# 04_AudioCodec.net
KiCad netlist of a schematic drawn in Altium Designer
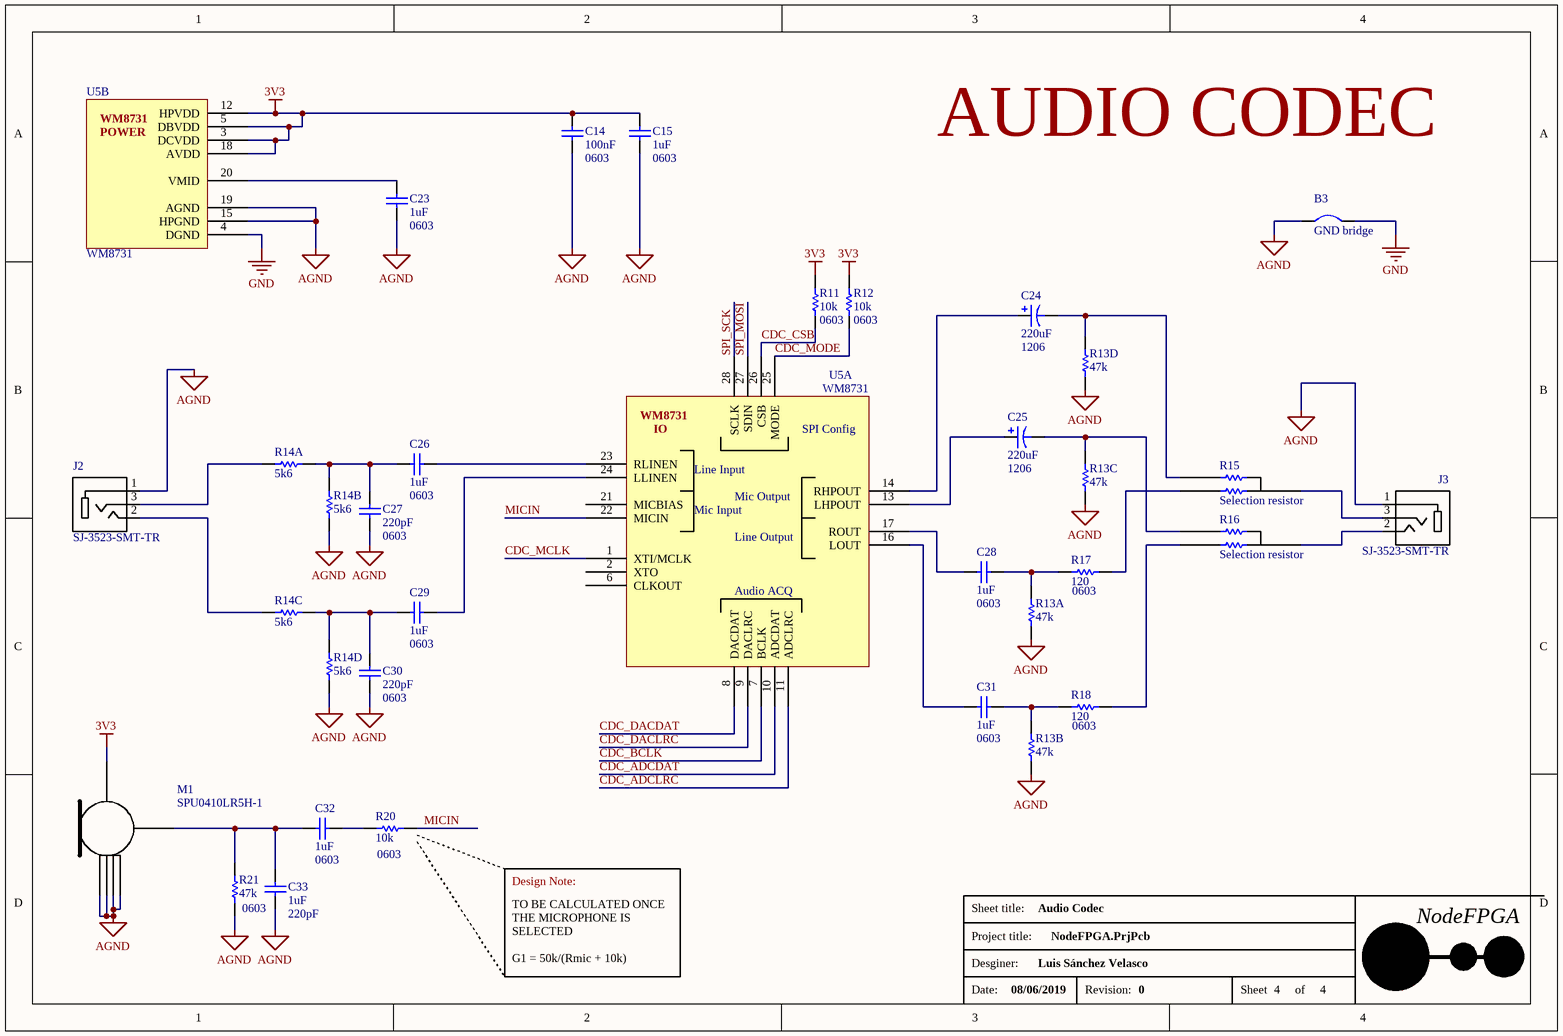
[diagram p0: 04_AudioCodec.SchDoc]

(export (version "E")
  (design (tool "Eeschema 10.0.6"))
  (components
    (comp (ref "B3") (value "GND bridge") (footprint "Bridge") (libsource (lib "NodeFPGA") (part "Bridge")))
    (comp (ref "C14")
      (value "100nF")
      (footprint "0603 CAP")
      (description "Capacitor")
      (fields (field (name "PACKAGE") "0603") (field (name "Comment") "Ceramic capacitor"))
      (libsource (lib "NodeFPGA") (part "Capacitor"))
    )
    (comp (ref "C15")
      (value "1uF")
      (footprint "0603 CAP")
      (description "Capacitor")
      (fields (field (name "PACKAGE") "0603") (field (name "Comment") "Ceramic capacitor"))
      (libsource (lib "NodeFPGA") (part "Capacitor"))
    )
    (comp (ref "C23")
      (value "1uF")
      (footprint "0603 CAP")
      (description "Capacitor")
      (fields (field (name "PACKAGE") "0603") (field (name "Comment") "Ceramic capacitor"))
      (libsource (lib "NodeFPGA") (part "Capacitor"))
    )
    (comp (ref "C24")
      (value "220uF")
      (footprint "CAPCP3216X16N")
      (description "Capacitor Electrolitic")
      (fields (field (name "PACKAGE") "1206") (field (name "AUTHOR") "Jaime Jiménez Ortega"))
      (libsource (lib "NodeFPGA") (part "Capacitor Electrolitic"))
    )
    (comp (ref "C25")
      (value "220uF")
      (footprint "CAPCP3216X16N")
      (description "Capacitor Electrolitic")
      (fields (field (name "PACKAGE") "1206") (field (name "AUTHOR") "Jaime Jiménez Ortega"))
      (libsource (lib "NodeFPGA") (part "Capacitor Electrolitic"))
    )
    (comp (ref "C26")
      (value "1uF")
      (footprint "0603 CAP")
      (description "Capacitor")
      (fields (field (name "PACKAGE") "0603") (field (name "Comment") "Ceramic capacitor"))
      (libsource (lib "NodeFPGA") (part "Capacitor"))
    )
    (comp (ref "C27")
      (value "220pF")
      (footprint "0603 CAP")
      (description "Capacitor")
      (fields (field (name "PACKAGE") "0603") (field (name "Comment") "Ceramic capacitor"))
      (libsource (lib "NodeFPGA") (part "Capacitor"))
    )
    (comp (ref "C28")
      (value "1uF")
      (footprint "0603 CAP")
      (description "Capacitor")
      (fields (field (name "PACKAGE") "0603") (field (name "Comment") "Ceramic capacitor"))
      (libsource (lib "NodeFPGA") (part "Capacitor"))
    )
    (comp (ref "C29")
      (value "1uF")
      (footprint "0603 CAP")
      (description "Capacitor")
      (fields (field (name "PACKAGE") "0603") (field (name "Comment") "Ceramic capacitor"))
      (libsource (lib "NodeFPGA") (part "Capacitor"))
    )
    (comp (ref "C30")
      (value "220pF")
      (footprint "0603 CAP")
      (description "Capacitor")
      (fields (field (name "PACKAGE") "0603") (field (name "Comment") "Ceramic capacitor"))
      (libsource (lib "NodeFPGA") (part "Capacitor"))
    )
    (comp (ref "C31")
      (value "1uF")
      (footprint "0603 CAP")
      (description "Capacitor")
      (fields (field (name "PACKAGE") "0603") (field (name "Comment") "Ceramic capacitor"))
      (libsource (lib "NodeFPGA") (part "Capacitor"))
    )
    (comp (ref "C32")
      (value "1uF")
      (footprint "0603 CAP")
      (description "Capacitor")
      (fields (field (name "PACKAGE") "0603") (field (name "Comment") "Ceramic capacitor"))
      (libsource (lib "NodeFPGA") (part "Capacitor"))
    )
    (comp (ref "C33")
      (value "1uF")
      (footprint "0603 CAP")
      (description "Capacitor")
      (fields (field (name "PACKAGE") "220pF") (field (name "Comment") "Ceramic capacitor"))
      (libsource (lib "NodeFPGA") (part "Capacitor"))
    )
    (comp (ref "J2")
      (value "SJ-3523-SMT-TR")
      (footprint "CUI_SJ-3523-SMT-TR")
      (libsource (lib "NodeFPGA") (part "SJ-3523-SMT-TR"))
    )
    (comp (ref "J3")
      (value "SJ-3523-SMT-TR")
      (footprint "CUI_SJ-3523-SMT-TR")
      (libsource (lib "NodeFPGA") (part "SJ-3523-SMT-TR"))
    )
    (comp (ref "M1")
      (value "SPU0410LR5H-1")
      (footprint "SPU0410LR5H-1")
      (description "MEMS Microphone")
      (libsource (lib "NodeFPGA") (part "SPU0410LR5H-1"))
    )
    (comp (ref "R11")
      (value "10k")
      (footprint "Resistencia 0603")
      (description "Resistor")
      (fields (field (name "PACKAGE") "0603"))
      (libsource (lib "NodeFPGA") (part "Resistor"))
    )
    (comp (ref "R12")
      (value "10k")
      (footprint "Resistencia 0603")
      (description "Resistor")
      (fields (field (name "PACKAGE") "0603"))
      (libsource (lib "NodeFPGA") (part "Resistor"))
    )
    (comp (ref "R13")
      (value "47k")
      (description "4 resistors in smd array configuration")
      (fields (field (name "Comment") "Resistor array"))
      (libsource (lib "NodeFPGA") (part "ResistorArray_4"))
    )
    (comp (ref "R14")
      (value "5k6")
      (description "4 resistors in smd array configuration")
      (fields (field (name "Comment") "Resistor array"))
      (libsource (lib "NodeFPGA") (part "ResistorArray_4"))
    )
    (comp (ref "R15") (value "Selection resistor") (libsource (lib "NodeFPGA") (part "SelectionResistor")))
    (comp (ref "R16") (value "Selection resistor") (libsource (lib "NodeFPGA") (part "SelectionResistor")))
    (comp (ref "R17")
      (value "120")
      (footprint "Resistencia 0603")
      (description "Resistor")
      (fields (field (name "PACKAGE") "0603"))
      (libsource (lib "NodeFPGA") (part "Resistor"))
    )
    (comp (ref "R18")
      (value "120")
      (footprint "Resistencia 0603")
      (description "Resistor")
      (fields (field (name "PACKAGE") "0603"))
      (libsource (lib "NodeFPGA") (part "Resistor"))
    )
    (comp (ref "R20")
      (value "10k")
      (footprint "Resistencia 0603")
      (description "Resistor")
      (fields (field (name "PACKAGE") "0603"))
      (libsource (lib "NodeFPGA") (part "Resistor"))
    )
    (comp (ref "R21")
      (value "47k")
      (footprint "Resistencia 0603")
      (description "Resistor")
      (fields (field (name "PACKAGE") "0603"))
      (libsource (lib "NodeFPGA") (part "Resistor"))
    )
    (comp (ref "U5")
      (value "WM8731")
      (footprint "WM8731")
      (description "Portable Internet Audio CODEC with Headphone Driver  and Programmable Sample Rates")
      (libsource (lib "NodeFPGA") (part "WM8731"))
    )
  )
  (nets
    (net (code "1") (name "/CDC_ADCDAT") (class "Default")
      (node (ref "U5") (pin "10") (pinfunction "ADCDAT_10") (pintype "passive"))
    )
    (net (code "2") (name "/CDC_ADCLRC") (class "Default")
      (node (ref "U5") (pin "11") (pinfunction "ADCLRC_11") (pintype "passive"))
    )
    (net (code "3") (name "/CDC_BCLK") (class "Default")
      (node (ref "U5") (pin "7") (pinfunction "BCLK_7") (pintype "passive"))
    )
    (net (code "4") (name "/CDC_CSB") (class "Default")
      (node (ref "R11") (pin "1") (pinfunction "1_1") (pintype "passive"))
      (node (ref "U5") (pin "26") (pinfunction "CSB_26") (pintype "passive"))
    )
    (net (code "5") (name "/CDC_DACDAT") (class "Default")
      (node (ref "U5") (pin "8") (pinfunction "DACDAT_8") (pintype "passive"))
    )
    (net (code "6") (name "/CDC_DACLRC") (class "Default")
      (node (ref "U5") (pin "9") (pinfunction "DACLRC_9") (pintype "passive"))
    )
    (net (code "7") (name "/CDC_MCLK") (class "Default")
      (node (ref "U5") (pin "1") (pinfunction "XTI/MCLK_1") (pintype "passive"))
    )
    (net (code "8") (name "/CDC_MODE") (class "Default")
      (node (ref "R12") (pin "1") (pinfunction "1_1") (pintype "passive"))
      (node (ref "U5") (pin "25") (pinfunction "MODE_25") (pintype "passive"))
    )
    (net (code "9") (name "/MICIN") (class "Default")
      (node (ref "R20") (pin "2") (pinfunction "2_2") (pintype "passive"))
      (node (ref "U5") (pin "22") (pinfunction "MICIN_22") (pintype "passive"))
    )
    (net (code "10") (name "/SPI_MOSI") (class "Default")
      (node (ref "U5") (pin "27") (pinfunction "SDIN_27") (pintype "passive"))
    )
    (net (code "11") (name "/SPI_SCK") (class "Default")
      (node (ref "U5") (pin "28") (pinfunction "SCLK_28") (pintype "passive"))
    )
    (net (code "12") (name "3V3") (class "Default")
      (node (ref "C14") (pin "1") (pinfunction "1_1") (pintype "passive"))
      (node (ref "C15") (pin "1") (pinfunction "1_1") (pintype "passive"))
      (node (ref "M1") (pin "4") (pinfunction "4_4") (pintype "passive"))
      (node (ref "R11") (pin "2") (pinfunction "2_2") (pintype "passive"))
      (node (ref "R12") (pin "2") (pinfunction "2_2") (pintype "passive"))
      (node (ref "U5") (pin "12") (pinfunction "HPVDD_12") (pintype "passive"))
      (node (ref "U5") (pin "18") (pinfunction "AVDD_18") (pintype "passive"))
      (node (ref "U5") (pin "3") (pinfunction "DCVDD_3") (pintype "passive"))
      (node (ref "U5") (pin "5") (pinfunction "DBVDD_5") (pintype "passive"))
    )
    (net (code "13") (name "AGND") (class "Default")
      (node (ref "B3") (pin "1") (pinfunction "1_1") (pintype "passive"))
      (node (ref "C14") (pin "2") (pinfunction "2_2") (pintype "passive"))
      (node (ref "C15") (pin "2") (pinfunction "2_2") (pintype "passive"))
      (node (ref "C23") (pin "2") (pinfunction "2_2") (pintype "passive"))
      (node (ref "C27") (pin "2") (pinfunction "2_2") (pintype "passive"))
      (node (ref "C30") (pin "2") (pinfunction "2_2") (pintype "passive"))
      (node (ref "C33") (pin "2") (pinfunction "2_2") (pintype "passive"))
      (node (ref "J2") (pin "1") (pinfunction "1_1") (pintype "passive"))
      (node (ref "J3") (pin "1") (pinfunction "1_1") (pintype "passive"))
      (node (ref "M1") (pin "2") (pinfunction "2_2") (pintype "passive"))
      (node (ref "M1") (pin "3") (pinfunction "3_3") (pintype "passive"))
      (node (ref "M1") (pin "5") (pinfunction "5_5") (pintype "passive"))
      (node (ref "M1") (pin "6") (pinfunction "6_6") (pintype "passive"))
      (node (ref "R13") (pin "5") (pinfunction "5_5") (pintype "passive"))
      (node (ref "R13") (pin "6") (pinfunction "6_6") (pintype "passive"))
      (node (ref "R13") (pin "7") (pinfunction "7_7") (pintype "passive"))
      (node (ref "R13") (pin "8") (pinfunction "8_8") (pintype "passive"))
      (node (ref "R14") (pin "2") (pinfunction "2_2") (pintype "passive"))
      (node (ref "R14") (pin "4") (pinfunction "4_4") (pintype "passive"))
      (node (ref "R21") (pin "1") (pinfunction "1_1") (pintype "passive"))
      (node (ref "U5") (pin "15") (pinfunction "HPGND_15") (pintype "passive"))
      (node (ref "U5") (pin "19") (pinfunction "AGND_19") (pintype "passive"))
    )
    (net (code "14") (name "GND") (class "Default")
      (node (ref "B3") (pin "2") (pinfunction "2_2") (pintype "passive"))
      (node (ref "U5") (pin "4") (pinfunction "DGND_4") (pintype "passive"))
    )
    (net (code "15") (name "Net-(C24-Pad2)") (class "Default")
      (node (ref "C24") (pin "2") (pinfunction "2_2") (pintype "passive"))
      (node (ref "R13") (pin "4") (pinfunction "4_4") (pintype "passive"))
      (node (ref "R15") (pin "1") (pinfunction "1_1") (pintype "passive"))
    )
    (net (code "16") (name "Net-(C25-Pad2)") (class "Default")
      (node (ref "C25") (pin "2") (pinfunction "2_2") (pintype "passive"))
      (node (ref "R13") (pin "3") (pinfunction "3_3") (pintype "passive"))
      (node (ref "R16") (pin "1") (pinfunction "1_1") (pintype "passive"))
    )
    (net (code "17") (name "Net-(C26-Pad1)") (class "Default")
      (node (ref "C26") (pin "1") (pinfunction "1_1") (pintype "passive"))
      (node (ref "C27") (pin "1") (pinfunction "1_1") (pintype "passive"))
      (node (ref "R14") (pin "7") (pinfunction "7_7") (pintype "passive"))
      (node (ref "R14") (pin "8") (pinfunction "8_8") (pintype "passive"))
    )
    (net (code "18") (name "Net-(C28-Pad2)") (class "Default")
      (node (ref "C28") (pin "2") (pinfunction "2_2") (pintype "passive"))
      (node (ref "R13") (pin "1") (pinfunction "1_1") (pintype "passive"))
      (node (ref "R17") (pin "1") (pinfunction "1_1") (pintype "passive"))
    )
    (net (code "19") (name "Net-(C29-Pad2)") (class "Default")
      (node (ref "C29") (pin "2") (pinfunction "2_2") (pintype "passive"))
      (node (ref "C30") (pin "1") (pinfunction "1_1") (pintype "passive"))
      (node (ref "R14") (pin "5") (pinfunction "5_5") (pintype "passive"))
      (node (ref "R14") (pin "6") (pinfunction "6_6") (pintype "passive"))
    )
    (net (code "20") (name "Net-(C31-Pad2)") (class "Default")
      (node (ref "C31") (pin "2") (pinfunction "2_2") (pintype "passive"))
      (node (ref "R13") (pin "2") (pinfunction "2_2") (pintype "passive"))
      (node (ref "R18") (pin "1") (pinfunction "1_1") (pintype "passive"))
    )
    (net (code "21") (name "Net-(C32-Pad1)") (class "Default")
      (node (ref "C32") (pin "1") (pinfunction "1_1") (pintype "passive"))
      (node (ref "R20") (pin "1") (pinfunction "1_1") (pintype "passive"))
    )
    (net (code "22") (name "Net-(C32-Pad2)") (class "Default")
      (node (ref "C32") (pin "2") (pinfunction "2_2") (pintype "passive"))
      (node (ref "C33") (pin "1") (pinfunction "1_1") (pintype "passive"))
      (node (ref "M1") (pin "1") (pinfunction "1_1") (pintype "passive"))
      (node (ref "R21") (pin "2") (pinfunction "2_2") (pintype "passive"))
    )
    (net (code "23") (name "Net-(J2-Pad2)") (class "Default")
      (node (ref "J2") (pin "2") (pinfunction "2_2") (pintype "passive"))
      (node (ref "R14") (pin "3") (pinfunction "3_3") (pintype "passive"))
    )
    (net (code "24") (name "Net-(J2-Pad3)") (class "Default")
      (node (ref "J2") (pin "3") (pinfunction "3_3") (pintype "passive"))
      (node (ref "R14") (pin "1") (pinfunction "1_1") (pintype "passive"))
    )
    (net (code "25") (name "Net-(J3-Pad2)") (class "Default")
      (node (ref "J3") (pin "2") (pinfunction "2_2") (pintype "passive"))
      (node (ref "R16") (pin "2") (pinfunction "2_2") (pintype "passive"))
    )
    (net (code "26") (name "Net-(J3-Pad3)") (class "Default")
      (node (ref "J3") (pin "3") (pinfunction "3_3") (pintype "passive"))
      (node (ref "R15") (pin "2") (pinfunction "2_2") (pintype "passive"))
    )
    (net (code "27") (name "Net-(R15-Pad3)") (class "Default")
      (node (ref "R15") (pin "3") (pinfunction "3_3") (pintype "passive"))
      (node (ref "R17") (pin "2") (pinfunction "2_2") (pintype "passive"))
    )
    (net (code "28") (name "Net-(R16-Pad3)") (class "Default")
      (node (ref "R16") (pin "3") (pinfunction "3_3") (pintype "passive"))
      (node (ref "R18") (pin "2") (pinfunction "2_2") (pintype "passive"))
    )
    (net (code "29") (name "Net-(U5A-LHPOUT)") (class "Default")
      (node (ref "C25") (pin "1") (pinfunction "1_1") (pintype "passive"))
      (node (ref "U5") (pin "13") (pinfunction "LHPOUT_13") (pintype "passive"))
    )
    (net (code "30") (name "Net-(U5A-LLINEN)") (class "Default")
      (node (ref "C29") (pin "1") (pinfunction "1_1") (pintype "passive"))
      (node (ref "U5") (pin "24") (pinfunction "LLINEN_24") (pintype "passive"))
    )
    (net (code "31") (name "Net-(U5A-LOUT)") (class "Default")
      (node (ref "C31") (pin "1") (pinfunction "1_1") (pintype "passive"))
      (node (ref "U5") (pin "16") (pinfunction "LOUT_16") (pintype "passive"))
    )
    (net (code "32") (name "Net-(U5A-RHPOUT)") (class "Default")
      (node (ref "C24") (pin "1") (pinfunction "1_1") (pintype "passive"))
      (node (ref "U5") (pin "14") (pinfunction "RHPOUT_14") (pintype "passive"))
    )
    (net (code "33") (name "Net-(U5A-RLINEN)") (class "Default")
      (node (ref "C26") (pin "2") (pinfunction "2_2") (pintype "passive"))
      (node (ref "U5") (pin "23") (pinfunction "RLINEN_23") (pintype "passive"))
    )
    (net (code "34") (name "Net-(U5A-ROUT)") (class "Default")
      (node (ref "C28") (pin "1") (pinfunction "1_1") (pintype "passive"))
      (node (ref "U5") (pin "17") (pinfunction "ROUT_17") (pintype "passive"))
    )
    (net (code "35") (name "Net-(U5B-VMID)") (class "Default")
      (node (ref "C23") (pin "1") (pinfunction "1_1") (pintype "passive"))
      (node (ref "U5") (pin "20") (pinfunction "VMID_20") (pintype "passive"))
    )
    (net (code "36") (name "unconnected-(U5A-CLKOUT-Pad6)") (class "Default")
      (node (ref "U5") (pin "6") (pinfunction "CLKOUT_6") (pintype "passive"))
    )
    (net (code "37") (name "unconnected-(U5A-MICBIAS-Pad21)") (class "Default")
      (node (ref "U5") (pin "21") (pinfunction "MICBIAS_21") (pintype "passive"))
    )
    (net (code "38") (name "unconnected-(U5A-XTO-Pad2)") (class "Default")
      (node (ref "U5") (pin "2") (pinfunction "XTO_2") (pintype "passive"))
    )
  )
)
